# power-breather.net
KiCad netlist of a schematic drawn in Altium Designer
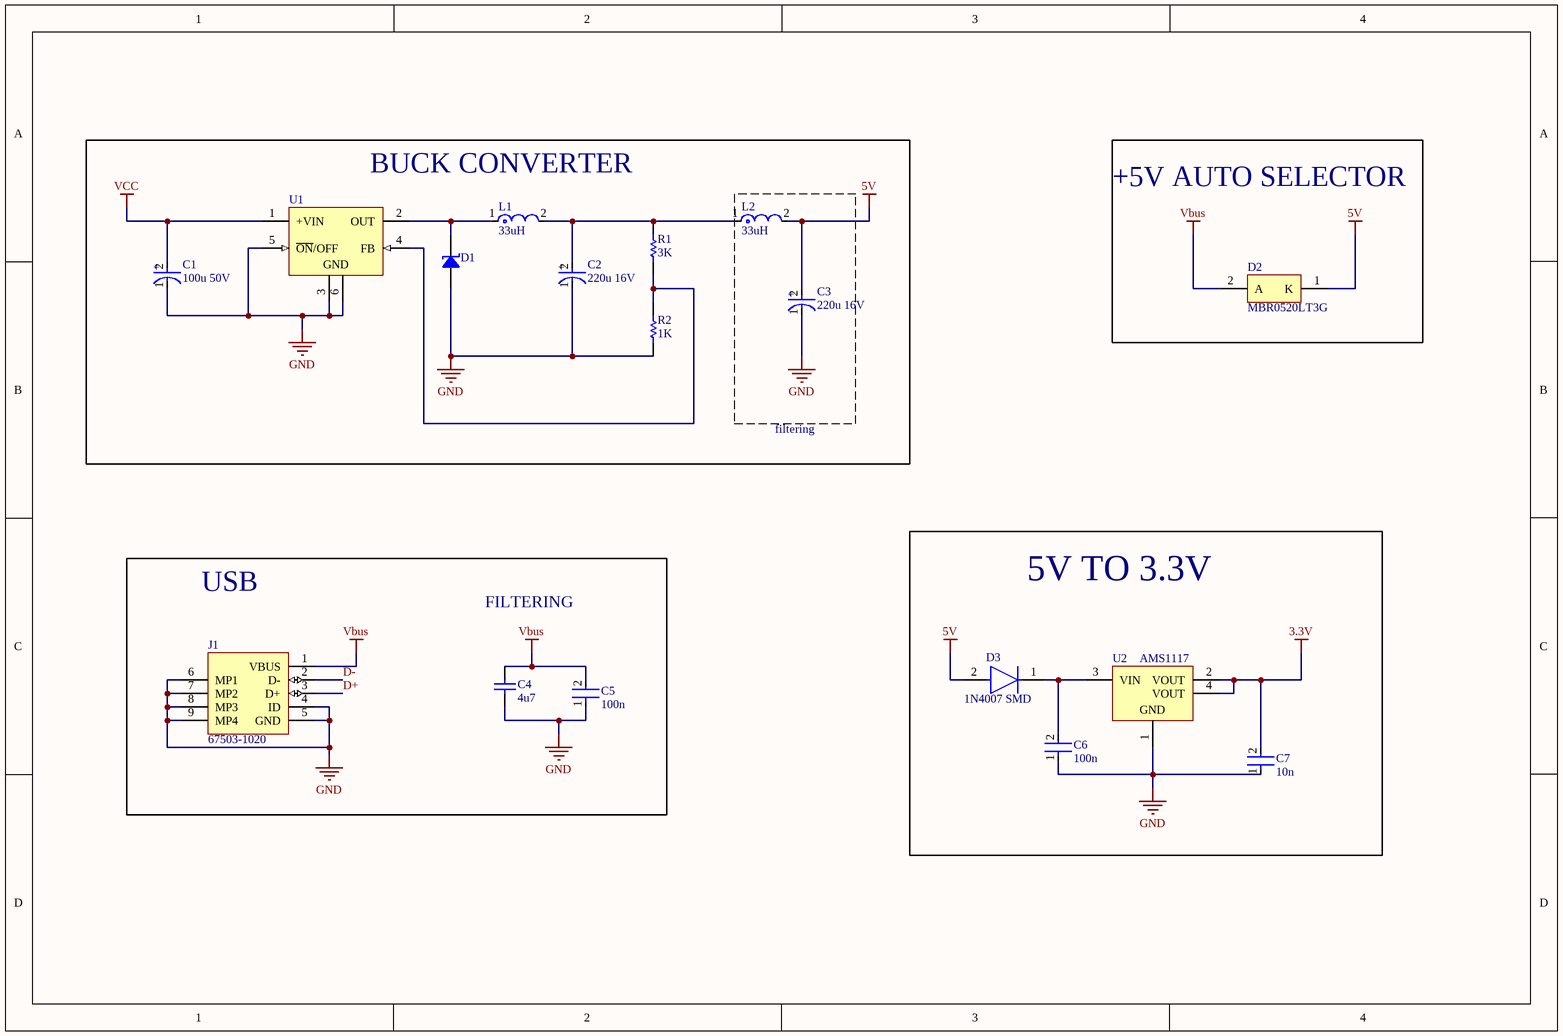
[diagram p0: power-breather.SchDoc]

(export (version "E")
  (design (tool "Eeschema 10.0.6"))
  (components
    (comp (ref "C1")
      (value "100u 50V")
      (footprint "FP-UKA1H101MPD1TD-MFG")
      (description "CAP ALUM 100UF 20% 50V RADIAL")
      (fields (field (name "TOLERANCE") "20%"))
      (libsource (lib "Altium Content Vault") (part "203bc49f2ac43e59fd269a8c329ed05"))
    )
    (comp (ref "C2")
      (value "220u 16V")
      (footprint "FP-UKA1H101MPD1TD-MFG")
      (description "CAP ALUM 100UF 20% 50V RADIAL")
      (fields (field (name "TOLERANCE") "20%"))
      (libsource (lib "Altium Content Vault") (part "203bc49f2ac43e59fd269a8c329ed05"))
    )
    (comp (ref "C3")
      (value "220u 16V")
      (footprint "FP-UKA1H101MPD1TD-MFG")
      (description "CAP ALUM 100UF 20% 50V RADIAL")
      (fields (field (name "TOLERANCE") "20%"))
      (libsource (lib "Altium Content Vault") (part "203bc49f2ac43e59fd269a8c329ed05"))
    )
    (comp (ref "C4")
      (value "4u7")
      (footprint "CAPC2013X135X45NL10T25")
      (fields (field (name "MANUFACTURER") "Murata") (field (name "PART NUMBER") "GRM21BR72E103KW03L"))
      (libsource (lib "Altium Content Vault") (part "CAP"))
    )
    (comp (ref "C5")
      (value "100n")
      (footprint "FP-GRM188-0_1-e0_2_0_55-IPC_A")
      (description "Chip Multilayer Ceramic Capacitors for General Purpose, 0603, 10uF, X5R, 15%, 20%, 6.3V")
      (fields (field (name "VOLTAGE") "6.3V") (field (name "TOLERANCE") "20%"))
      (libsource (lib "Altium Content Vault") (part "02cd4be3c70576c341d710602a673aa"))
    )
    (comp (ref "C6")
      (value "100n")
      (footprint "FP-GRM188-0_1-e0_2_0_55-IPC_A")
      (description "Chip Multilayer Ceramic Capacitors for General Purpose, 0603, 10uF, X5R, 15%, 20%, 6.3V")
      (fields (field (name "VOLTAGE") "6.3V") (field (name "TOLERANCE") "20%"))
      (libsource (lib "Altium Content Vault") (part "02cd4be3c70576c341d710602a673aa"))
    )
    (comp (ref "C7")
      (value "10n")
      (footprint "FP-GRM188-0_1-e0_2_0_55-IPC_A")
      (description "Chip Multilayer Ceramic Capacitors for General Purpose, 0603, 10uF, X5R, 15%, 20%, 6.3V")
      (fields (field (name "VOLTAGE") "6.3V") (field (name "TOLERANCE") "20%"))
      (libsource (lib "Altium Content Vault") (part "02cd4be3c70576c341d710602a673aa"))
    )
    (comp (ref "D1")
      (value "VTVS3V3GSMF-M3-08")
      (footprint "SMF DO-219AB")
      (description "ESD PROTECTION DIODE DO-219AB-M3")
      (fields (field (name "MANUFACTURER") "Vishay Semiconductor Diodes Division"))
      (libsource (lib "Celestial Altium Library - altium_library") (part "DIODE TVS UNI"))
    )
    (comp (ref "D2")
      (value "MBR0520LT3G")
      (footprint "ONSC-SOD-123-2-425-04_V")
      (description "Schottky Power Rectifier, 2-Pin SOD-123, Pb-Free, Tape and Reel")
      (fields (field (name "MANUFACTURER") "On Semiconductor"))
      (libsource (lib "Altium Content Vault") (part "ONSC-D-K1A2-2_A"))
    )
    (comp (ref "D3")
      (value "1N4007 SMD")
      (footprint "FP-1N4007_SMD-IPC_C")
      (description "Rectifier, 1Kv, 1A, Do-214Ac Rohs Compliant: Yes")
      (libsource (lib "Altium Content Vault") (part "d7152d700b627762746794eb795d46e"))
    )
    (comp (ref "J1")
      (value "67503-1020")
      (footprint "MOLX-67503-1020_V")
      (description "USB, MINI, SMD, RA KME04-USBMU03A01")
      (fields (field (name "MANUFACTURER") "Molex"))
      (libsource (lib "Altium Content Vault") (part "MOLX-67503-1020"))
    )
    (comp (ref "L1")
      (value "33uH")
      (footprint "FP-DEM10050C-MFG")
      (description "Shielded Wirewound Inductor 33uH 20% 2500mA 0.0936Ω SMD")
      (fields (field (name "TOLERANCE") "20%"))
      (libsource (lib "Altium Content Vault") (part "4cc4b267dca4c8e51f7102f422741d8"))
    )
    (comp (ref "L2")
      (value "33uH")
      (footprint "FP-DEM10050C-MFG")
      (description "Shielded Wirewound Inductor 33uH 20% 2500mA 0.0936Ω SMD")
      (fields (field (name "TOLERANCE") "20%"))
      (libsource (lib "Altium Content Vault") (part "4cc4b267dca4c8e51f7102f422741d8"))
    )
    (comp (ref "R1")
      (value "3K")
      (footprint "RESC2013X60X35ML10T20")
      (description "Chip Resistor, 1 KOhm, +/- 1%, 125 mW, -55 to 155 degC, 0805 (2012 Metric), RoHS, Tape and Reel")
      (fields (field (name "TOLERANCE") "1%") (field (name "MANUFACTURER") "Yageo"))
      (libsource (lib "Altium Content Vault") (part "RES-2"))
    )
    (comp (ref "R2")
      (value "1K")
      (footprint "RESC2013X60X35ML10T20")
      (description "Chip Resistor, 1 KOhm, +/- 1%, 125 mW, -55 to 155 degC, 0805 (2012 Metric), RoHS, Tape and Reel")
      (fields (field (name "TOLERANCE") "1%") (field (name "MANUFACTURER") "Yageo"))
      (libsource (lib "Altium Content Vault") (part "RES-2"))
    )
    (comp (ref "U1")
      (value "LM2596SX-ADJ/NOPB")
      (footprint "KTT0005B_L")
      (fields (field (name "PARTNUMBER") "LM2596") (field (name "MANUFACTURER") "Texas Instruments"))
      (libsource (lib "Altium Content Vault") (part "TI-LM2596-TO-263-5"))
    )
    (comp (ref "U2")
      (value "AMS1117")
      (footprint "SOT-223_M")
      (description "1A, Low Drop Positive Voltage Regulator, 3.3V, 4-Pin SOT-223, Tape and Reel")
      (libsource (lib "Altium Content Vault") (part "PM-REG-LD1117-SOT4"))
    )
  )
  (nets
    (net (code "1") (name "/D+") (class "Default")
      (node (ref "J1") (pin "3") (pinfunction "D+_3") (pintype "bidirectional"))
    )
    (net (code "2") (name "/D-") (class "Default")
      (node (ref "J1") (pin "2") (pinfunction "D-_2") (pintype "bidirectional"))
    )
    (net (code "3") (name "3.3V") (class "Default")
      (node (ref "C7") (pin "2") (pinfunction "2_2") (pintype "passive"))
      (node (ref "U2") (pin "2") (pinfunction "VOUT_2") (pintype "power_in"))
      (node (ref "U2") (pin "4") (pinfunction "VOUT_4") (pintype "power_in"))
    )
    (net (code "4") (name "5V") (class "Default")
      (node (ref "C3") (pin "2") (pinfunction "A_2") (pintype "passive"))
      (node (ref "D2") (pin "1") (pinfunction "K_1") (pintype "passive"))
      (node (ref "D3") (pin "2") (pinfunction "A_2") (pintype "passive"))
      (node (ref "L2") (pin "2") (pinfunction "2_2") (pintype "passive"))
    )
    (net (code "5") (name "GND") (class "Default")
      (node (ref "C1") (pin "1") (pinfunction "C_1") (pintype "passive"))
      (node (ref "C2") (pin "1") (pinfunction "C_1") (pintype "passive"))
      (node (ref "C3") (pin "1") (pinfunction "C_1") (pintype "passive"))
      (node (ref "C4") (pin "1") (pinfunction "1_1") (pintype "passive"))
      (node (ref "C5") (pin "1") (pinfunction "1_1") (pintype "passive"))
      (node (ref "C6") (pin "1") (pinfunction "1_1") (pintype "passive"))
      (node (ref "C7") (pin "1") (pinfunction "1_1") (pintype "passive"))
      (node (ref "D1") (pin "1") (pinfunction "1_1") (pintype "passive"))
      (node (ref "J1") (pin "4") (pinfunction "ID_4") (pintype "passive"))
      (node (ref "J1") (pin "5") (pinfunction "GND_5") (pintype "power_in"))
      (node (ref "J1") (pin "6") (pinfunction "MP1_6") (pintype "passive"))
      (node (ref "J1") (pin "7") (pinfunction "MP2_7") (pintype "passive"))
      (node (ref "J1") (pin "8") (pinfunction "MP3_8") (pintype "passive"))
      (node (ref "J1") (pin "9") (pinfunction "MP4_9") (pintype "passive"))
      (node (ref "R2") (pin "1") (pinfunction "1_1") (pintype "passive"))
      (node (ref "U1") (pin "3") (pinfunction "GND_3") (pintype "power_in"))
      (node (ref "U1") (pin "5") (pinfunction "~{ON}/OFF_5") (pintype "input"))
      (node (ref "U1") (pin "6") (pinfunction "GND_6") (pintype "power_in"))
      (node (ref "U2") (pin "1") (pinfunction "GND_1") (pintype "power_in"))
    )
    (net (code "6") (name "Net-(C2-A)") (class "Default")
      (node (ref "C2") (pin "2") (pinfunction "A_2") (pintype "passive"))
      (node (ref "L1") (pin "2") (pinfunction "2_2") (pintype "passive"))
      (node (ref "L2") (pin "1") (pinfunction "1_1") (pintype "passive"))
      (node (ref "R1") (pin "2") (pinfunction "2_2") (pintype "passive"))
    )
    (net (code "7") (name "Net-(D3-C)") (class "Default")
      (node (ref "C6") (pin "2") (pinfunction "2_2") (pintype "passive"))
      (node (ref "D3") (pin "1") (pinfunction "C_1") (pintype "passive"))
      (node (ref "U2") (pin "3") (pinfunction "VIN_3") (pintype "power_in"))
    )
    (net (code "8") (name "Net-(U1-FB)") (class "Default")
      (node (ref "R1") (pin "1") (pinfunction "1_1") (pintype "passive"))
      (node (ref "R2") (pin "2") (pinfunction "2_2") (pintype "passive"))
      (node (ref "U1") (pin "4") (pinfunction "FB_4") (pintype "input"))
    )
    (net (code "9") (name "Net-(U1-OUT)") (class "Default")
      (node (ref "D1") (pin "2") (pinfunction "2_2") (pintype "passive"))
      (node (ref "L1") (pin "1") (pinfunction "1_1") (pintype "passive"))
      (node (ref "U1") (pin "2") (pinfunction "OUT_2") (pintype "power_in"))
    )
    (net (code "10") (name "VCC") (class "Default")
      (node (ref "C1") (pin "2") (pinfunction "A_2") (pintype "passive"))
      (node (ref "U1") (pin "1") (pinfunction "+VIN_1") (pintype "power_in"))
    )
    (net (code "11") (name "Vbus") (class "Default")
      (node (ref "C4") (pin "2") (pinfunction "2_2") (pintype "passive"))
      (node (ref "C5") (pin "2") (pinfunction "2_2") (pintype "passive"))
      (node (ref "D2") (pin "2") (pinfunction "A_2") (pintype "passive"))
      (node (ref "J1") (pin "1") (pinfunction "VBUS_1") (pintype "power_in"))
    )
  )
)
